# 12VSLA_UPS.net
KiCad netlist of a schematic drawn in EAGLE
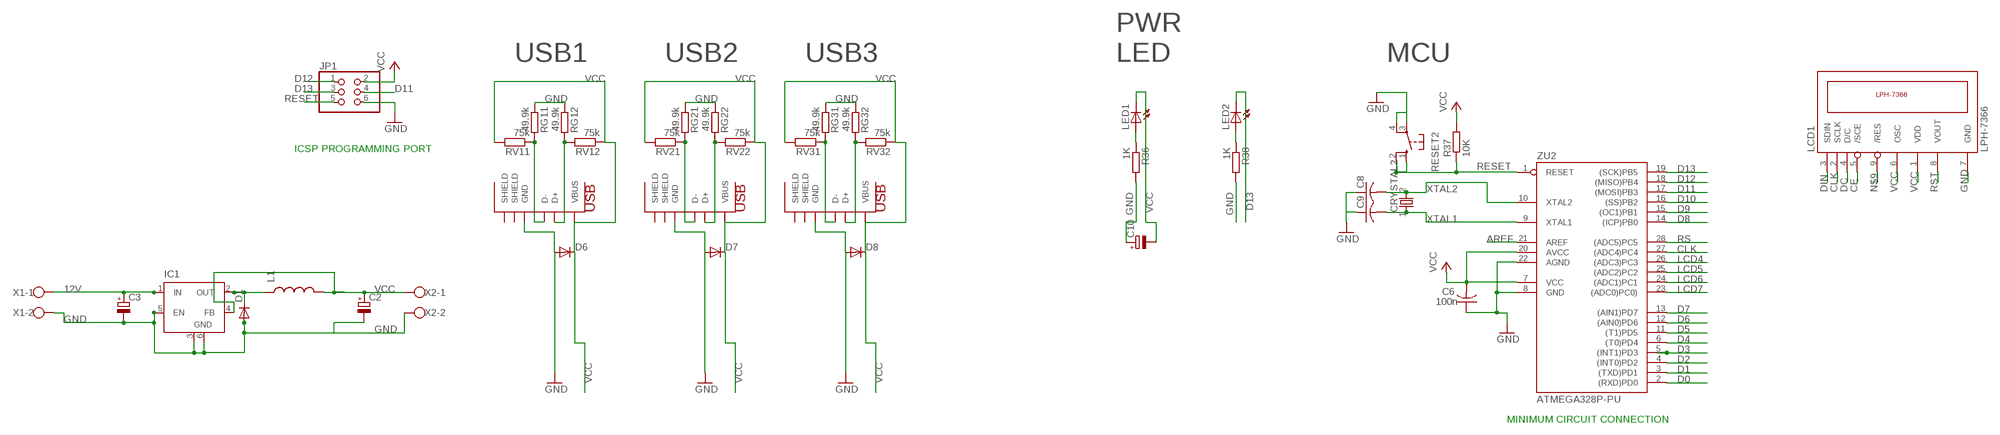
[diagram p0: schematic, sheet 1]

(export (version "E")
  (design (tool "Eeschema 10.0.6"))
  (components
    (comp (ref "C2")
      (value "CPOL-EU153CLV-0605")
      (footprint "eagle-import:153CLV-0605")
      (libsource (lib "eagle-import") (part "CPOL-EU153CLV-0605"))
    )
    (comp (ref "C3")
      (value "CPOL-EU153CLV-0605")
      (footprint "eagle-import:153CLV-0605")
      (libsource (lib "eagle-import") (part "CPOL-EU153CLV-0605"))
    )
    (comp (ref "C6")
      (value "100n")
      (footprint "eagle-import:C1206K")
      (libsource (lib "eagle-import") (part "C-USC1206K"))
    )
    (comp (ref "C8")
      (value "C-USC1206K")
      (footprint "eagle-import:C1206K")
      (libsource (lib "eagle-import") (part "C-USC1206K"))
    )
    (comp (ref "C9")
      (value "C-USC1206K")
      (footprint "eagle-import:C1206K")
      (libsource (lib "eagle-import") (part "C-USC1206K"))
    )
    (comp (ref "C10")
      (value "CPOL-EU153CLV-0807")
      (footprint "eagle-import:153CLV-0807")
      (libsource (lib "eagle-import") (part "CPOL-EU153CLV-0807"))
    )
    (comp (ref "CRYSTAL2")
      (value "CRYSTAL2PIN")
      (footprint "eagle-import:CRYSTAL-2PIN")
      (libsource (lib "eagle-import") (part "CRYSTAL2PIN"))
    )
    (comp (ref "D1")
      (value "DIODE-DO-214AC")
      (footprint "eagle-import:DO-214AC")
      (libsource (lib "eagle-import") (part "DIODE-DO-214AC"))
    )
    (comp (ref "D6")
      (value "DIODESMA-ALT")
      (footprint "eagle-import:SMA-DIODE_ALT")
      (libsource (lib "eagle-import") (part "DIODESMA-ALT"))
    )
    (comp (ref "D7")
      (value "DIODESMA-ALT")
      (footprint "eagle-import:SMA-DIODE_ALT")
      (libsource (lib "eagle-import") (part "DIODESMA-ALT"))
    )
    (comp (ref "D8")
      (value "DIODESMA-ALT")
      (footprint "eagle-import:SMA-DIODE_ALT")
      (libsource (lib "eagle-import") (part "DIODESMA-ALT"))
    )
    (comp (ref "IC1")
      (value "LM2596S")
      (footprint "eagle-import:TO263-5")
      (libsource (lib "eagle-import") (part "LM2596S"))
    )
    (comp (ref "JP1")
      (value "PINHD-2X3")
      (footprint "eagle-import:2X03")
      (libsource (lib "eagle-import") (part "PINHD-2X3"))
    )
    (comp (ref "L1")
      (value "INDUCTORPWR")
      (footprint "eagle-import:CDRH125")
      (libsource (lib "eagle-import") (part "INDUCTORPWR"))
    )
    (comp (ref "LCD1")
      (value "LPH-7366")
      (footprint "eagle-import:LPH-7366")
      (libsource (lib "eagle-import") (part "LPH-7366"))
    )
    (comp (ref "LED1")
      (value "LED3MM")
      (footprint "eagle-import:LED3MM")
      (libsource (lib "eagle-import") (part "LED3MM"))
    )
    (comp (ref "LED2")
      (value "LED3MM")
      (footprint "eagle-import:LED3MM")
      (libsource (lib "eagle-import") (part "LED3MM"))
    )
    (comp (ref "R36")
      (value "1K")
      (footprint "eagle-import:M1206")
      (libsource (lib "eagle-import") (part "resistor_R-EU_M1206"))
    )
    (comp (ref "R37")
      (value "10K")
      (footprint "eagle-import:M1206")
      (libsource (lib "eagle-import") (part "R-EU_M1206"))
    )
    (comp (ref "R38")
      (value "1K")
      (footprint "eagle-import:M1206")
      (libsource (lib "eagle-import") (part "resistor_R-EU_M1206"))
    )
    (comp (ref "RESET2")
      (value "10-XX")
      (footprint "eagle-import:B3F-10XX")
      (fields (field (name "MPN") "B3F-1000"))
      (libsource (lib "eagle-import") (part "10-XX"))
    )
    (comp (ref "RG11")
      (value "49.9k")
      (footprint "eagle-import:M1206")
      (libsource (lib "eagle-import") (part "resistor_R-EU_M1206"))
    )
    (comp (ref "RG12")
      (value "49.9k")
      (footprint "eagle-import:M1206")
      (libsource (lib "eagle-import") (part "resistor_R-EU_M1206"))
    )
    (comp (ref "RG21")
      (value "49.9k")
      (footprint "eagle-import:M1206")
      (libsource (lib "eagle-import") (part "resistor_R-EU_M1206"))
    )
    (comp (ref "RG22")
      (value "49.9k")
      (footprint "eagle-import:M1206")
      (libsource (lib "eagle-import") (part "resistor_R-EU_M1206"))
    )
    (comp (ref "RG31")
      (value "49.9k")
      (footprint "eagle-import:M1206")
      (libsource (lib "eagle-import") (part "resistor_R-EU_M1206"))
    )
    (comp (ref "RG32")
      (value "49.9k")
      (footprint "eagle-import:M1206")
      (libsource (lib "eagle-import") (part "resistor_R-EU_M1206"))
    )
    (comp (ref "RV11")
      (value "75k")
      (footprint "eagle-import:M1206")
      (libsource (lib "eagle-import") (part "resistor_R-EU_M1206"))
    )
    (comp (ref "RV12")
      (value "75k")
      (footprint "eagle-import:M1206")
      (libsource (lib "eagle-import") (part "resistor_R-EU_M1206"))
    )
    (comp (ref "RV21")
      (value "75k")
      (footprint "eagle-import:M1206")
      (libsource (lib "eagle-import") (part "resistor_R-EU_M1206"))
    )
    (comp (ref "RV22")
      (value "75k")
      (footprint "eagle-import:M1206")
      (libsource (lib "eagle-import") (part "resistor_R-EU_M1206"))
    )
    (comp (ref "RV31")
      (value "75k")
      (footprint "eagle-import:M1206")
      (libsource (lib "eagle-import") (part "resistor_R-EU_M1206"))
    )
    (comp (ref "RV32")
      (value "75k")
      (footprint "eagle-import:M1206")
      (libsource (lib "eagle-import") (part "resistor_R-EU_M1206"))
    )
    (comp (ref "USB1")
      (value "USB-A-H")
      (footprint "eagle-import:USB-A-H")
      (libsource (lib "eagle-import") (part "USB-A-H"))
    )
    (comp (ref "USB2")
      (value "USB-A-H")
      (footprint "eagle-import:USB-A-H")
      (libsource (lib "eagle-import") (part "USB-A-H"))
    )
    (comp (ref "USB3")
      (value "USB-A-H")
      (footprint "eagle-import:USB-A-H")
      (libsource (lib "eagle-import") (part "USB-A-H"))
    )
    (comp (ref "X1")
      (value "W237-102")
      (footprint "eagle-import:W237-102")
      (fields (field (name "MPN") "237-102"))
      (libsource (lib "eagle-import") (part "W237-102"))
    )
    (comp (ref "X2")
      (value "W237-102")
      (footprint "eagle-import:W237-102")
      (fields (field (name "MPN") "237-102"))
      (libsource (lib "eagle-import") (part "W237-102"))
    )
    (comp (ref "ZU2")
      (value "ATMEGA328P-PU")
      (footprint "eagle-import:DIL28-3")
      (libsource (lib "eagle-import") (part "ATMEGA328P-PU"))
    )
  )
  (nets
    (net (code "1") (name "/12V") (class "Default")
      (node (ref "C3") (pin "+") (pinfunction "+_+") (pintype "passive"))
      (node (ref "IC1") (pin "1") (pinfunction "IN_1") (pintype "input"))
      (node (ref "X1") (pin "1") (pinfunction "KL_1") (pintype "passive"))
    )
    (net (code "2") (name "/AREF") (class "Default")
      (node (ref "ZU2") (pin "21") (pinfunction "AREF_21") (pintype "passive"))
    )
    (net (code "3") (name "/CE") (class "Default")
      (node (ref "LCD1") (pin "5") (pinfunction "/SCE_5") (pintype "input"))
    )
    (net (code "4") (name "/CLK") (class "Default")
      (node (ref "LCD1") (pin "2") (pinfunction "SCLK_2") (pintype "input"))
      (node (ref "ZU2") (pin "27") (pinfunction "(ADC4)PC4_27") (pintype "bidirectional"))
    )
    (net (code "5") (name "/D0") (class "Default")
      (node (ref "ZU2") (pin "2") (pinfunction "(RXD)PD0_2") (pintype "bidirectional"))
    )
    (net (code "6") (name "/D1") (class "Default")
      (node (ref "ZU2") (pin "3") (pinfunction "(TXD)PD1_3") (pintype "bidirectional"))
    )
    (net (code "7") (name "/D2") (class "Default")
      (node (ref "ZU2") (pin "4") (pinfunction "(INT0)PD2_4") (pintype "bidirectional"))
    )
    (net (code "8") (name "/D3") (class "Default")
      (node (ref "ZU2") (pin "5") (pinfunction "(INT1)PD3_5") (pintype "bidirectional"))
    )
    (net (code "9") (name "/D4") (class "Default")
      (node (ref "ZU2") (pin "6") (pinfunction "(T0)PD4_6") (pintype "bidirectional"))
    )
    (net (code "10") (name "/D5") (class "Default")
      (node (ref "ZU2") (pin "11") (pinfunction "(T1)PD5_11") (pintype "bidirectional"))
    )
    (net (code "11") (name "/D6") (class "Default")
      (node (ref "ZU2") (pin "12") (pinfunction "(AIN0)PD6_12") (pintype "bidirectional"))
    )
    (net (code "12") (name "/D7") (class "Default")
      (node (ref "ZU2") (pin "13") (pinfunction "(AIN1)PD7_13") (pintype "bidirectional"))
    )
    (net (code "13") (name "/D8") (class "Default")
      (node (ref "ZU2") (pin "14") (pinfunction "(ICP)PB0_14") (pintype "bidirectional"))
    )
    (net (code "14") (name "/D9") (class "Default")
      (node (ref "ZU2") (pin "15") (pinfunction "(OC1)PB1_15") (pintype "bidirectional"))
    )
    (net (code "15") (name "/D10") (class "Default")
      (node (ref "ZU2") (pin "16") (pinfunction "(SS)PB2_16") (pintype "bidirectional"))
    )
    (net (code "16") (name "/D11") (class "Default")
      (node (ref "JP1") (pin "4") (pinfunction "4_4") (pintype "passive"))
      (node (ref "ZU2") (pin "17") (pinfunction "(MOSI)PB3_17") (pintype "bidirectional"))
    )
    (net (code "17") (name "/D12") (class "Default")
      (node (ref "JP1") (pin "1") (pinfunction "1_1") (pintype "passive"))
      (node (ref "ZU2") (pin "18") (pinfunction "(MISO)PB4_18") (pintype "bidirectional"))
    )
    (net (code "18") (name "/D13") (class "Default")
      (node (ref "JP1") (pin "3") (pinfunction "3_3") (pintype "passive"))
      (node (ref "LED2") (pin "K") (pinfunction "C_K") (pintype "passive"))
      (node (ref "ZU2") (pin "19") (pinfunction "(SCK)PB5_19") (pintype "bidirectional"))
    )
    (net (code "19") (name "/DC") (class "Default")
      (node (ref "LCD1") (pin "4") (pinfunction "D/C_4") (pintype "input"))
    )
    (net (code "20") (name "/DIN") (class "Default")
      (node (ref "LCD1") (pin "3") (pinfunction "SDIN_3") (pintype "input"))
    )
    (net (code "21") (name "/LCD4") (class "Default")
      (node (ref "ZU2") (pin "26") (pinfunction "(ADC3)PC3_26") (pintype "bidirectional"))
    )
    (net (code "22") (name "/LCD5") (class "Default")
      (node (ref "ZU2") (pin "25") (pinfunction "(ADC2)PC2_25") (pintype "bidirectional"))
    )
    (net (code "23") (name "/LCD6") (class "Default")
      (node (ref "ZU2") (pin "24") (pinfunction "(ADC1)PC1_24") (pintype "bidirectional"))
    )
    (net (code "24") (name "/LCD7") (class "Default")
      (node (ref "ZU2") (pin "23") (pinfunction "(ADC0)PC0)_23") (pintype "bidirectional"))
    )
    (net (code "25") (name "/N$9") (class "Default")
      (node (ref "LCD1") (pin "9") (pinfunction "/RES_9") (pintype "input"))
    )
    (net (code "26") (name "/RESET") (class "Default")
      (node (ref "JP1") (pin "5") (pinfunction "5_5") (pintype "passive"))
      (node (ref "R37") (pin "1") (pinfunction "1_1") (pintype "passive"))
      (node (ref "RESET2") (pin "1") (pinfunction "S_1") (pintype "passive"))
      (node (ref "RESET2") (pin "2") (pinfunction "S1_2") (pintype "passive"))
      (node (ref "ZU2") (pin "1") (pinfunction "RESET_1") (pintype "input"))
    )
    (net (code "27") (name "/RS") (class "Default")
      (node (ref "ZU2") (pin "28") (pinfunction "(ADC5)PC5_28") (pintype "bidirectional"))
    )
    (net (code "28") (name "/RST") (class "Default")
      (node (ref "LCD1") (pin "8") (pinfunction "VOUT_8") (pintype "passive"))
    )
    (net (code "29") (name "/XTAL1") (class "Default")
      (node (ref "C9") (pin "2") (pinfunction "2_2") (pintype "passive"))
      (node (ref "CRYSTAL2") (pin "1") (pinfunction "1_1") (pintype "passive"))
      (node (ref "ZU2") (pin "9") (pinfunction "XTAL1_9") (pintype "bidirectional"))
    )
    (net (code "30") (name "/XTAL2") (class "Default")
      (node (ref "C8") (pin "2") (pinfunction "2_2") (pintype "passive"))
      (node (ref "CRYSTAL2") (pin "2") (pinfunction "2_2") (pintype "passive"))
      (node (ref "ZU2") (pin "10") (pinfunction "XTAL2_10") (pintype "bidirectional"))
    )
    (net (code "31") (name "GND") (class "Default")
      (node (ref "C10") (pin "+") (pinfunction "+_+") (pintype "passive"))
      (node (ref "C2") (pin "-") (pinfunction "-_-") (pintype "passive"))
      (node (ref "C3") (pin "-") (pinfunction "-_-") (pintype "passive"))
      (node (ref "C6") (pin "1") (pinfunction "1_1") (pintype "passive"))
      (node (ref "C8") (pin "1") (pinfunction "1_1") (pintype "passive"))
      (node (ref "C9") (pin "1") (pinfunction "1_1") (pintype "passive"))
      (node (ref "D1") (pin "2") (pinfunction "A_2") (pintype "passive"))
      (node (ref "D6") (pin "A") (pinfunction "A_A") (pintype "passive"))
      (node (ref "D7") (pin "A") (pinfunction "A_A") (pintype "passive"))
      (node (ref "D8") (pin "A") (pinfunction "A_A") (pintype "passive"))
      (node (ref "IC1") (pin "3") (pinfunction "GND_3") (pintype "power_in"))
      (node (ref "IC1") (pin "5") (pinfunction "EN_5") (pintype "input"))
      (node (ref "IC1") (pin "6") (pinfunction "GND_6") (pintype "power_in"))
      (node (ref "JP1") (pin "6") (pinfunction "6_6") (pintype "passive"))
      (node (ref "LCD1") (pin "7") (pinfunction "GND_7") (pintype "power_in"))
      (node (ref "R36") (pin "2") (pinfunction "2_2") (pintype "passive"))
      (node (ref "R38") (pin "2") (pinfunction "2_2") (pintype "passive"))
      (node (ref "RESET2") (pin "3") (pinfunction "P_3") (pintype "passive"))
      (node (ref "RESET2") (pin "4") (pinfunction "P1_4") (pintype "passive"))
      (node (ref "RG11") (pin "1") (pinfunction "1_1") (pintype "passive"))
      (node (ref "RG12") (pin "1") (pinfunction "1_1") (pintype "passive"))
      (node (ref "RG21") (pin "1") (pinfunction "1_1") (pintype "passive"))
      (node (ref "RG22") (pin "1") (pinfunction "1_1") (pintype "passive"))
      (node (ref "RG31") (pin "1") (pinfunction "1_1") (pintype "passive"))
      (node (ref "RG32") (pin "1") (pinfunction "1_1") (pintype "passive"))
      (node (ref "USB1") (pin "GND") (pinfunction "GND_GND") (pintype "bidirectional"))
      (node (ref "USB2") (pin "GND") (pinfunction "GND_GND") (pintype "bidirectional"))
      (node (ref "USB3") (pin "GND") (pinfunction "GND_GND") (pintype "bidirectional"))
      (node (ref "X1") (pin "2") (pinfunction "KL_2") (pintype "passive"))
      (node (ref "X2") (pin "2") (pinfunction "KL_2") (pintype "passive"))
      (node (ref "ZU2") (pin "22") (pinfunction "AGND_22") (pintype "power_in"))
      (node (ref "ZU2") (pin "8") (pinfunction "GND_8") (pintype "power_in"))
    )
    (net (code "32") (name "Net-(D1-C)") (class "Default")
      (node (ref "D1") (pin "1") (pinfunction "C_1") (pintype "passive"))
      (node (ref "IC1") (pin "2") (pinfunction "OUT_2") (pintype "output"))
      (node (ref "L1") (pin "1") (pinfunction "1_1") (pintype "passive"))
    )
    (net (code "33") (name "Net-(LED1-PadA)") (class "Default")
      (node (ref "LED1") (pin "A") (pinfunction "A_A") (pintype "passive"))
      (node (ref "R36") (pin "1") (pinfunction "1_1") (pintype "passive"))
    )
    (net (code "34") (name "Net-(LED2-PadA)") (class "Default")
      (node (ref "LED2") (pin "A") (pinfunction "A_A") (pintype "passive"))
      (node (ref "R38") (pin "1") (pinfunction "1_1") (pintype "passive"))
    )
    (net (code "35") (name "Net-(RG11-Pad2)") (class "Default")
      (node (ref "RG11") (pin "2") (pinfunction "2_2") (pintype "passive"))
      (node (ref "RV11") (pin "1") (pinfunction "1_1") (pintype "passive"))
      (node (ref "USB1") (pin "D-") (pinfunction "D-_D-") (pintype "bidirectional"))
    )
    (net (code "36") (name "Net-(RG12-Pad2)") (class "Default")
      (node (ref "RG12") (pin "2") (pinfunction "2_2") (pintype "passive"))
      (node (ref "RV12") (pin "2") (pinfunction "2_2") (pintype "passive"))
      (node (ref "USB1") (pin "D+") (pinfunction "D+_D+") (pintype "bidirectional"))
    )
    (net (code "37") (name "Net-(RG21-Pad2)") (class "Default")
      (node (ref "RG21") (pin "2") (pinfunction "2_2") (pintype "passive"))
      (node (ref "RV21") (pin "1") (pinfunction "1_1") (pintype "passive"))
      (node (ref "USB2") (pin "D-") (pinfunction "D-_D-") (pintype "bidirectional"))
    )
    (net (code "38") (name "Net-(RG22-Pad2)") (class "Default")
      (node (ref "RG22") (pin "2") (pinfunction "2_2") (pintype "passive"))
      (node (ref "RV22") (pin "2") (pinfunction "2_2") (pintype "passive"))
      (node (ref "USB2") (pin "D+") (pinfunction "D+_D+") (pintype "bidirectional"))
    )
    (net (code "39") (name "Net-(RG31-Pad2)") (class "Default")
      (node (ref "RG31") (pin "2") (pinfunction "2_2") (pintype "passive"))
      (node (ref "RV31") (pin "1") (pinfunction "1_1") (pintype "passive"))
      (node (ref "USB3") (pin "D-") (pinfunction "D-_D-") (pintype "bidirectional"))
    )
    (net (code "40") (name "Net-(RG32-Pad2)") (class "Default")
      (node (ref "RG32") (pin "2") (pinfunction "2_2") (pintype "passive"))
      (node (ref "RV32") (pin "2") (pinfunction "2_2") (pintype "passive"))
      (node (ref "USB3") (pin "D+") (pinfunction "D+_D+") (pintype "bidirectional"))
    )
    (net (code "41") (name "VCC") (class "Default")
      (node (ref "C10") (pin "-") (pinfunction "-_-") (pintype "passive"))
      (node (ref "C2") (pin "+") (pinfunction "+_+") (pintype "passive"))
      (node (ref "C6") (pin "2") (pinfunction "2_2") (pintype "passive"))
      (node (ref "D6") (pin "C") (pinfunction "C_C") (pintype "passive"))
      (node (ref "D7") (pin "C") (pinfunction "C_C") (pintype "passive"))
      (node (ref "D8") (pin "C") (pinfunction "C_C") (pintype "passive"))
      (node (ref "IC1") (pin "4") (pinfunction "FB_4") (pintype "input"))
      (node (ref "JP1") (pin "2") (pinfunction "2_2") (pintype "passive"))
      (node (ref "L1") (pin "2") (pinfunction "2_2") (pintype "passive"))
      (node (ref "LCD1") (pin "1") (pinfunction "VDD_1") (pintype "power_in"))
      (node (ref "LCD1") (pin "6") (pinfunction "OSC_6") (pintype "passive"))
      (node (ref "LED1") (pin "K") (pinfunction "C_K") (pintype "passive"))
      (node (ref "R37") (pin "2") (pinfunction "2_2") (pintype "passive"))
      (node (ref "RV11") (pin "2") (pinfunction "2_2") (pintype "passive"))
      (node (ref "RV12") (pin "1") (pinfunction "1_1") (pintype "passive"))
      (node (ref "RV21") (pin "2") (pinfunction "2_2") (pintype "passive"))
      (node (ref "RV22") (pin "1") (pinfunction "1_1") (pintype "passive"))
      (node (ref "RV31") (pin "2") (pinfunction "2_2") (pintype "passive"))
      (node (ref "RV32") (pin "1") (pinfunction "1_1") (pintype "passive"))
      (node (ref "USB1") (pin "VBUS") (pinfunction "VBUS_VBUS") (pintype "bidirectional"))
      (node (ref "USB2") (pin "VBUS") (pinfunction "VBUS_VBUS") (pintype "bidirectional"))
      (node (ref "USB3") (pin "VBUS") (pinfunction "VBUS_VBUS") (pintype "bidirectional"))
      (node (ref "X2") (pin "1") (pinfunction "KL_1") (pintype "passive"))
      (node (ref "ZU2") (pin "20") (pinfunction "AVCC_20") (pintype "power_in"))
      (node (ref "ZU2") (pin "7") (pinfunction "VCC_7") (pintype "power_in"))
    )
    (net (code "42") (name "unconnected-(USB1-SHIELD-PadGND@1)") (class "Default")
      (node (ref "USB1") (pin "GND@1") (pinfunction "SHIELD_GND@1") (pintype "bidirectional"))
    )
    (net (code "43") (name "unconnected-(USB1-SHIELD-PadGND@2)") (class "Default")
      (node (ref "USB1") (pin "GND@2") (pinfunction "SHIELD_GND@2") (pintype "bidirectional"))
    )
    (net (code "44") (name "unconnected-(USB2-SHIELD-PadGND@1)") (class "Default")
      (node (ref "USB2") (pin "GND@1") (pinfunction "SHIELD_GND@1") (pintype "bidirectional"))
    )
    (net (code "45") (name "unconnected-(USB2-SHIELD-PadGND@2)") (class "Default")
      (node (ref "USB2") (pin "GND@2") (pinfunction "SHIELD_GND@2") (pintype "bidirectional"))
    )
    (net (code "46") (name "unconnected-(USB3-SHIELD-PadGND@1)") (class "Default")
      (node (ref "USB3") (pin "GND@1") (pinfunction "SHIELD_GND@1") (pintype "bidirectional"))
    )
    (net (code "47") (name "unconnected-(USB3-SHIELD-PadGND@2)") (class "Default")
      (node (ref "USB3") (pin "GND@2") (pinfunction "SHIELD_GND@2") (pintype "bidirectional"))
    )
  )
)
